# TPS54620.net
KiCad netlist of a schematic drawn in Altium Designer
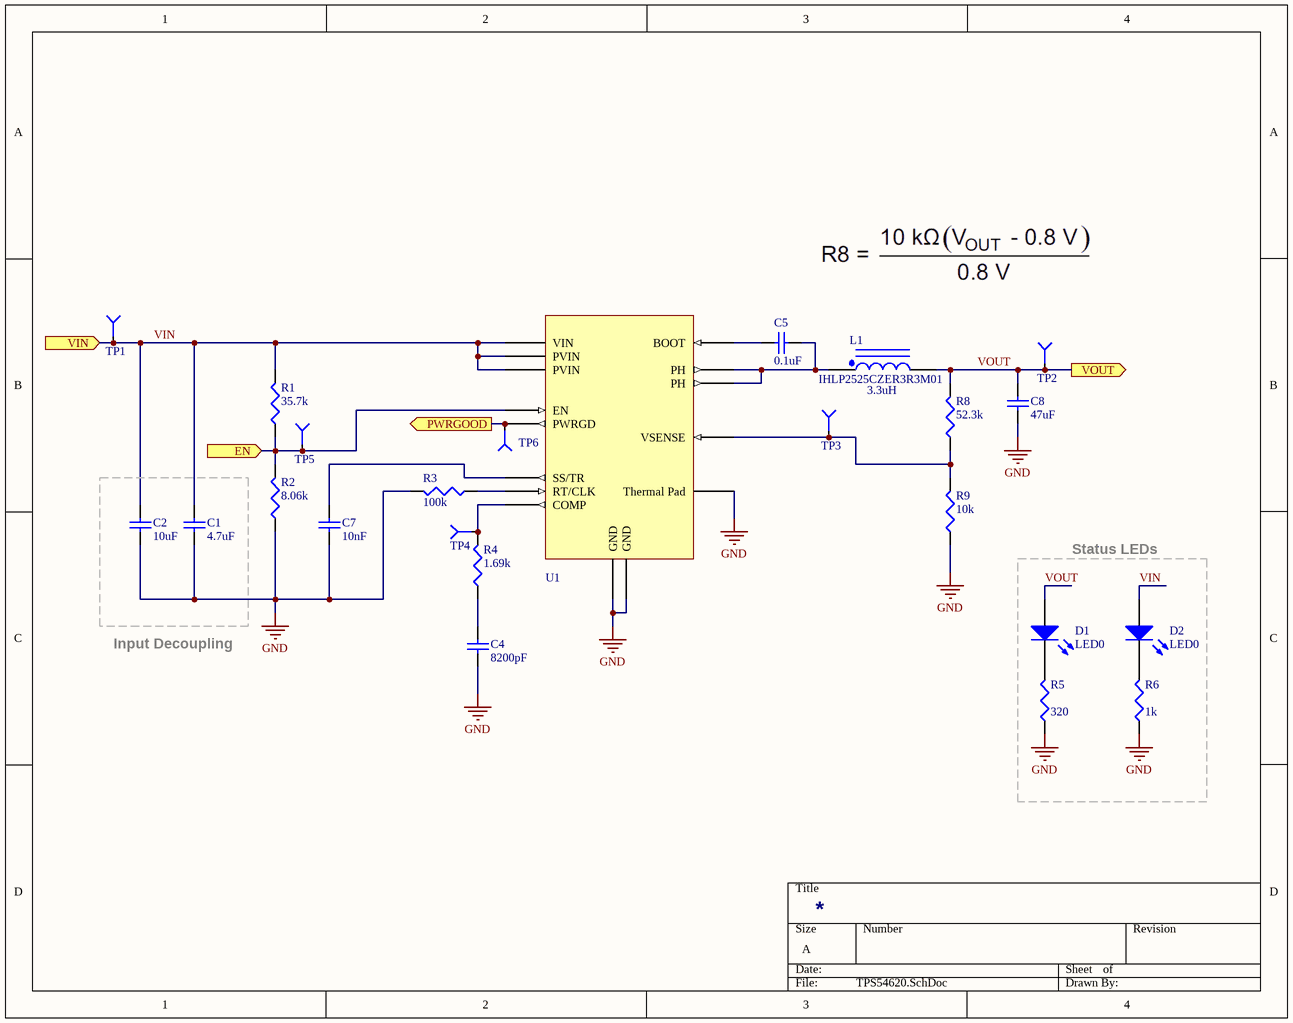
[diagram p0: TPS54620.SchDoc]

(export (version "E")
  (design (tool "Eeschema 10.0.6"))
  (components
    (comp (ref "C1")
      (value "4.7uF")
      (footprint "1608[0603]")
      (description "Capacitor (Semiconductor SIM Model)")
      (fields (field (name "Comment") "Cap") (field (name "PUBLISHER") "Altium Limited"))
      (libsource (lib "Miscellaneous Devices") (part "Cap Semi"))
    )
    (comp (ref "C2")
      (value "10uF")
      (footprint "1608[0603]")
      (description "Capacitor (Semiconductor SIM Model)")
      (fields (field (name "Comment") "Cap") (field (name "PUBLISHER") "Altium Limited"))
      (libsource (lib "Miscellaneous Devices") (part "Cap Semi"))
    )
    (comp (ref "C4")
      (value "8200pF")
      (footprint "1608[0603]")
      (description "Capacitor (Semiconductor SIM Model)")
      (fields (field (name "Comment") "Cap") (field (name "PUBLISHER") "Altium Limited"))
      (libsource (lib "Miscellaneous Devices") (part "Cap Semi"))
    )
    (comp (ref "C5")
      (value "0.1uF")
      (footprint "1608[0603]")
      (description "Capacitor (Semiconductor SIM Model)")
      (fields (field (name "Comment") "Cap") (field (name "PUBLISHER") "Altium Limited"))
      (libsource (lib "Miscellaneous Devices") (part "Cap Semi"))
    )
    (comp (ref "C7")
      (value "10nF")
      (footprint "1608[0603]")
      (description "Capacitor (Semiconductor SIM Model)")
      (fields (field (name "Comment") "Cap") (field (name "PUBLISHER") "Altium Limited"))
      (libsource (lib "Miscellaneous Devices") (part "Cap Semi"))
    )
    (comp (ref "C8")
      (value "47uF")
      (footprint "1608[0603]")
      (description "Capacitor (Semiconductor SIM Model)")
      (fields (field (name "Comment") "Cap") (field (name "PUBLISHER") "Altium Limited"))
      (libsource (lib "Miscellaneous Devices") (part "Cap Semi"))
    )
    (comp (ref "D1")
      (value "LED0")
      (footprint "0603 LED")
      (description "Typical INFRARED GaAs LED")
      (fields (field (name "PUBLISHER") "Altium Limited"))
      (libsource (lib "Miscellaneous Devices") (part "LED0"))
    )
    (comp (ref "D2")
      (value "LED0")
      (footprint "0603 LED")
      (description "Typical INFRARED GaAs LED")
      (fields (field (name "PUBLISHER") "Altium Limited"))
      (libsource (lib "Miscellaneous Devices") (part "LED0"))
    )
    (comp (ref "L1")
      (value "IHLP2525CZER3R3M01")
      (footprint "INDP6965X30M")
      (description "3.3uH Shielded Inductor")
      (fields (field (name "ALTIUM_VALUE") "3.3uH"))
      (libsource (lib "Miscellaneous Devices") (part "IHLP2525CZER3R3M01"))
    )
    (comp (ref "R1")
      (value "35.7k")
      (footprint "J1-0603")
      (description "Resistor")
      (fields (field (name "Comment") "Res3") (field (name "PUBLISHER") "Altium Limited"))
      (libsource (lib "Miscellaneous Devices") (part "Res3"))
    )
    (comp (ref "R2")
      (value "8.06k")
      (footprint "J1-0603")
      (description "Resistor")
      (fields (field (name "Comment") "Res3") (field (name "PUBLISHER") "Altium Limited"))
      (libsource (lib "Miscellaneous Devices") (part "Res3"))
    )
    (comp (ref "R3")
      (value "100k")
      (footprint "J1-0603")
      (description "Resistor")
      (fields (field (name "Comment") "Res3") (field (name "PUBLISHER") "Altium Limited"))
      (libsource (lib "Miscellaneous Devices") (part "Res3"))
    )
    (comp (ref "R4")
      (value "1.69k")
      (footprint "J1-0603")
      (description "Resistor")
      (fields (field (name "Comment") "Res3") (field (name "PUBLISHER") "Altium Limited"))
      (libsource (lib "Miscellaneous Devices") (part "Res3"))
    )
    (comp (ref "R5")
      (value "320")
      (footprint "J1-0603")
      (description "Resistor")
      (fields (field (name "Comment") "Res3") (field (name "PUBLISHER") "Altium Limited"))
      (libsource (lib "Miscellaneous Devices") (part "Res3"))
    )
    (comp (ref "R6")
      (value "1k")
      (footprint "J1-0603")
      (description "Resistor")
      (fields (field (name "Comment") "Res3") (field (name "PUBLISHER") "Altium Limited"))
      (libsource (lib "Miscellaneous Devices") (part "Res3"))
    )
    (comp (ref "R8")
      (value "52.3k")
      (footprint "J1-0603")
      (description "Resistor")
      (fields (field (name "Comment") "Res3") (field (name "PUBLISHER") "Altium Limited"))
      (libsource (lib "Miscellaneous Devices") (part "Res3"))
    )
    (comp (ref "R9")
      (value "10k")
      (footprint "J1-0603")
      (description "Resistor")
      (fields (field (name "Comment") "Res3") (field (name "PUBLISHER") "Altium Limited"))
      (libsource (lib "Miscellaneous Devices") (part "Res3"))
    )
    (comp (ref "TP1")
      (value "Test Point")
      (footprint "TESTPOINT_0.3mm")
      (libsource (lib "Miscellaneous Connectors") (part "Test Point"))
    )
    (comp (ref "TP2")
      (value "Test Point")
      (footprint "TESTPOINT_0.3mm")
      (libsource (lib "Miscellaneous Connectors") (part "Test Point"))
    )
    (comp (ref "TP3")
      (value "Test Point")
      (footprint "TESTPOINT_0.3mm")
      (libsource (lib "Miscellaneous Connectors") (part "Test Point"))
    )
    (comp (ref "TP4")
      (value "Test Point")
      (footprint "TESTPOINT_0.3mm")
      (libsource (lib "Miscellaneous Connectors") (part "Test Point"))
    )
    (comp (ref "TP5")
      (value "Test Point")
      (footprint "TESTPOINT_0.3mm")
      (libsource (lib "Miscellaneous Connectors") (part "Test Point"))
    )
    (comp (ref "TP6")
      (value "Test Point")
      (footprint "TESTPOINT_0.3mm")
      (libsource (lib "Miscellaneous Connectors") (part "Test Point"))
    )
    (comp (ref "U1")
      (value "Buck Regulator")
      (footprint "S-PVQFN-N14")
      (description "IC REG BUCK ADJ 6A SYNC 14VQFN")
      (fields
        (field (name "MANUFACTURER") "Texas Instruments")
        (field (name "MANUFACTURER PART NUMBER") "TPS54620RGYT")
      )
      (libsource (lib "Miscellaneous Devices") (part "TPS54620RGYT"))
    )
  )
  (nets
    (net (code "1") (name "/EN") (class "Default")
      (node (ref "R1") (pin "1") (pinfunction "1_1") (pintype "passive"))
      (node (ref "R2") (pin "2") (pinfunction "2_2") (pintype "passive"))
      (node (ref "TP5") (pin "TP") (pinfunction "TP_TP") (pintype "passive"))
      (node (ref "U1") (pin "10") (pinfunction "EN_10") (pintype "input"))
    )
    (net (code "2") (name "/PWRGOOD") (class "Default")
      (node (ref "TP6") (pin "TP") (pinfunction "TP_TP") (pintype "passive"))
      (node (ref "U1") (pin "14") (pinfunction "PWRGD_14") (pintype "output"))
    )
    (net (code "3") (name "/VIN") (class "Default")
      (node (ref "C1") (pin "1") (pinfunction "1_1") (pintype "passive"))
      (node (ref "C2") (pin "1") (pinfunction "1_1") (pintype "passive"))
      (node (ref "D2") (pin "1") (pinfunction "A_1") (pintype "passive"))
      (node (ref "R1") (pin "2") (pinfunction "2_2") (pintype "passive"))
      (node (ref "TP1") (pin "TP") (pinfunction "TP_TP") (pintype "passive"))
      (node (ref "U1") (pin "4") (pinfunction "PVIN_4") (pintype "power_in"))
      (node (ref "U1") (pin "5") (pinfunction "PVIN_5") (pintype "power_in"))
      (node (ref "U1") (pin "6") (pinfunction "VIN_6") (pintype "power_in"))
    )
    (net (code "4") (name "/VOUT") (class "Default")
      (node (ref "C8") (pin "2") (pinfunction "2_2") (pintype "passive"))
      (node (ref "D1") (pin "1") (pinfunction "A_1") (pintype "passive"))
      (node (ref "L1") (pin "2") (pinfunction "2_2") (pintype "passive"))
      (node (ref "R8") (pin "2") (pinfunction "2_2") (pintype "passive"))
      (node (ref "TP2") (pin "TP") (pinfunction "TP_TP") (pintype "passive"))
    )
    (net (code "5") (name "GND") (class "Default")
      (node (ref "C1") (pin "2") (pinfunction "2_2") (pintype "passive"))
      (node (ref "C2") (pin "2") (pinfunction "2_2") (pintype "passive"))
      (node (ref "C4") (pin "1") (pinfunction "1_1") (pintype "passive"))
      (node (ref "C7") (pin "1") (pinfunction "1_1") (pintype "passive"))
      (node (ref "C8") (pin "1") (pinfunction "1_1") (pintype "passive"))
      (node (ref "R2") (pin "1") (pinfunction "1_1") (pintype "passive"))
      (node (ref "R3") (pin "2") (pinfunction "2_2") (pintype "passive"))
      (node (ref "R5") (pin "1") (pinfunction "1_1") (pintype "passive"))
      (node (ref "R6") (pin "1") (pinfunction "1_1") (pintype "passive"))
      (node (ref "R9") (pin "1") (pinfunction "1_1") (pintype "passive"))
      (node (ref "U1") (pin "2") (pinfunction "GND_2") (pintype "power_in"))
      (node (ref "U1") (pin "3") (pinfunction "GND_3") (pintype "power_in"))
      (node (ref "U1") (pin "PAD") (pinfunction "Thermal_Pad_PAD") (pintype "passive"))
    )
    (net (code "6") (name "Net-(C4-Pad2)") (class "Default")
      (node (ref "C4") (pin "2") (pinfunction "2_2") (pintype "passive"))
      (node (ref "R4") (pin "1") (pinfunction "1_1") (pintype "passive"))
    )
    (net (code "7") (name "Net-(C5-Pad2)") (class "Default")
      (node (ref "C5") (pin "2") (pinfunction "2_2") (pintype "passive"))
      (node (ref "L1") (pin "1") (pinfunction "1_1") (pintype "passive"))
      (node (ref "U1") (pin "11") (pinfunction "PH_11") (pintype "output"))
      (node (ref "U1") (pin "12") (pinfunction "PH_12") (pintype "output"))
    )
    (net (code "8") (name "Net-(D1-K)") (class "Default")
      (node (ref "D1") (pin "2") (pinfunction "K_2") (pintype "passive"))
      (node (ref "R5") (pin "2") (pinfunction "2_2") (pintype "passive"))
    )
    (net (code "9") (name "Net-(D2-K)") (class "Default")
      (node (ref "D2") (pin "2") (pinfunction "K_2") (pintype "passive"))
      (node (ref "R6") (pin "2") (pinfunction "2_2") (pintype "passive"))
    )
    (net (code "10") (name "Net-(U1-BOOT)") (class "Default")
      (node (ref "C5") (pin "1") (pinfunction "1_1") (pintype "passive"))
      (node (ref "U1") (pin "13") (pinfunction "BOOT_13") (pintype "input"))
    )
    (net (code "11") (name "Net-(U1-COMP)") (class "Default")
      (node (ref "R4") (pin "2") (pinfunction "2_2") (pintype "passive"))
      (node (ref "TP4") (pin "TP") (pinfunction "TP_TP") (pintype "passive"))
      (node (ref "U1") (pin "8") (pinfunction "COMP_8") (pintype "output"))
    )
    (net (code "12") (name "Net-(U1-RT{slash}CLK)") (class "Default")
      (node (ref "R3") (pin "1") (pinfunction "1_1") (pintype "passive"))
      (node (ref "U1") (pin "1") (pinfunction "RT/CLK_1") (pintype "input"))
    )
    (net (code "13") (name "Net-(U1-SS{slash}TR)") (class "Default")
      (node (ref "C7") (pin "2") (pinfunction "2_2") (pintype "passive"))
      (node (ref "U1") (pin "9") (pinfunction "SS/TR_9") (pintype "output"))
    )
    (net (code "14") (name "Net-(U1-VSENSE)") (class "Default")
      (node (ref "R8") (pin "1") (pinfunction "1_1") (pintype "passive"))
      (node (ref "R9") (pin "2") (pinfunction "2_2") (pintype "passive"))
      (node (ref "TP3") (pin "TP") (pinfunction "TP_TP") (pintype "passive"))
      (node (ref "U1") (pin "7") (pinfunction "VSENSE_7") (pintype "input"))
    )
  )
)
